# SCH_MCP23X17_smaller_chips_2021-12-25.net
KiCad netlist of a schematic drawn in EasyEDA
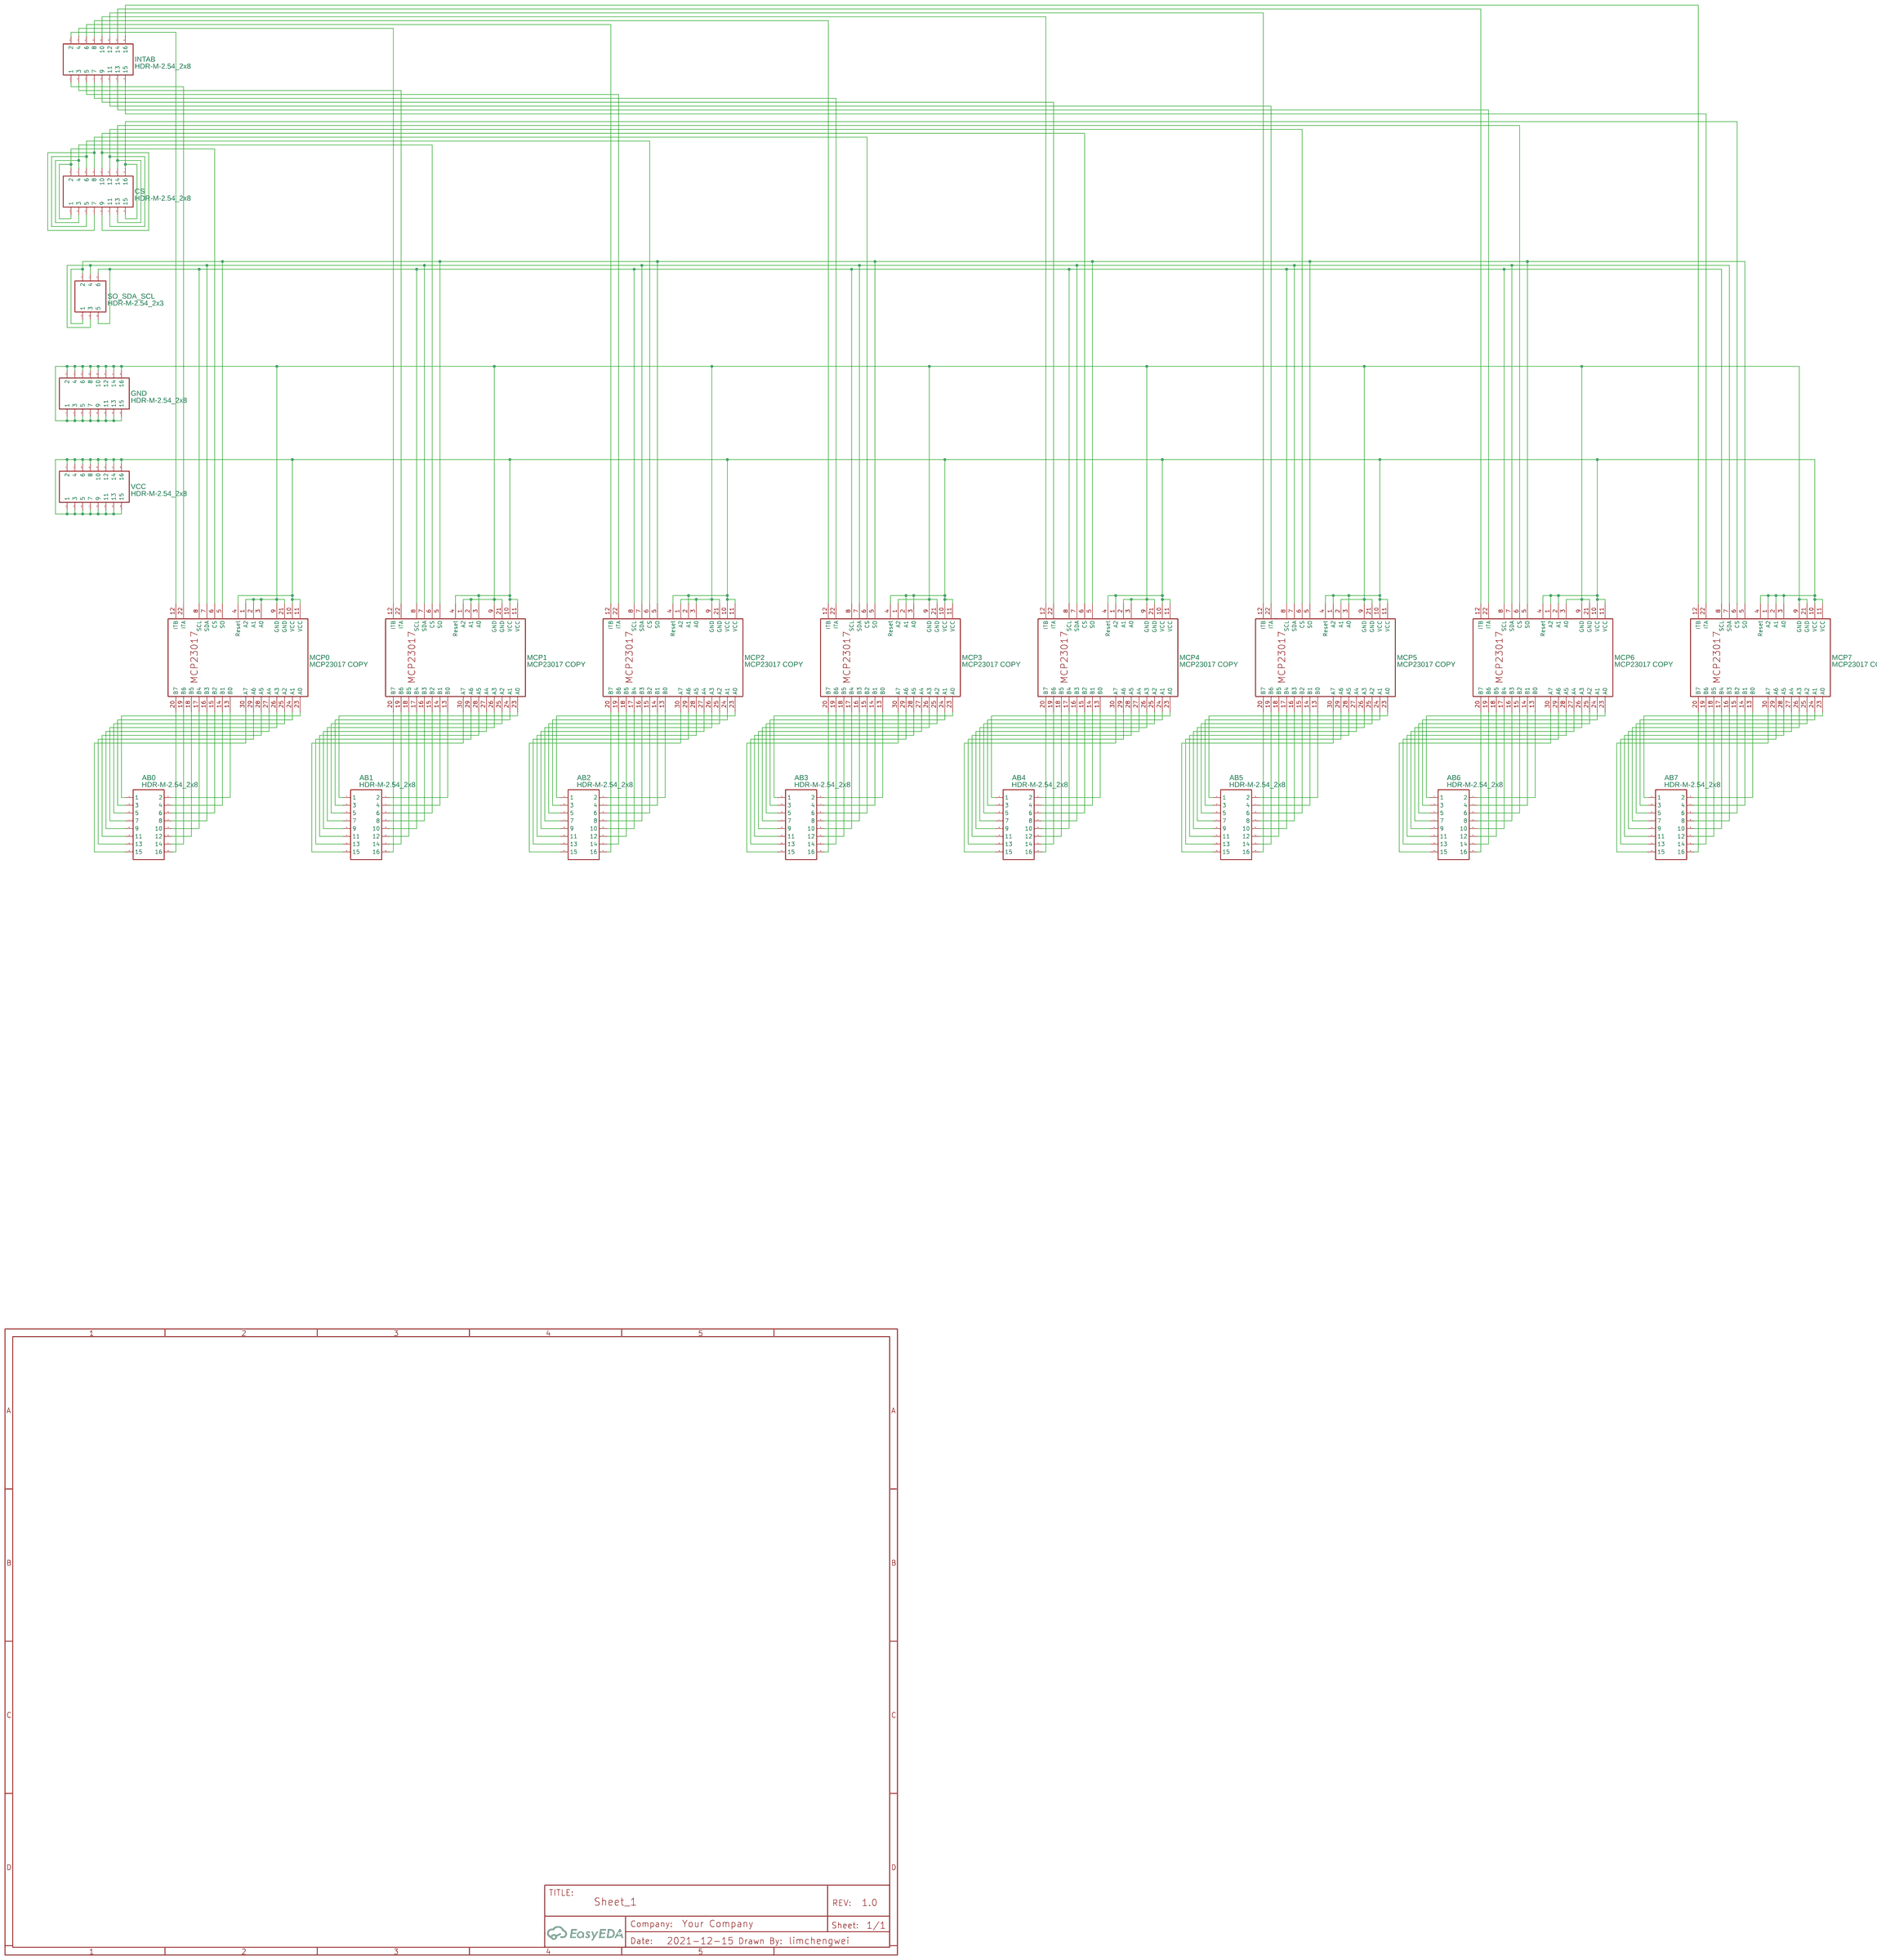
[diagram p0: schematic sheet]

(export (version "E")
  (design (tool "Eeschema 10.0.6"))
  (components
    (comp (ref "AB0")
      (value "HDR-M-2.54_2x8")
      (fields (field (name "BOM_Supplier Part") "C68234"))
      (libsource (lib "") (part "HDR-M-2.54_2x8"))
    )
    (comp (ref "AB1")
      (value "HDR-M-2.54_2x8")
      (fields (field (name "BOM_Supplier Part") "C68234"))
      (libsource (lib "") (part "HDR-M-2.54_2x8"))
    )
    (comp (ref "AB2")
      (value "HDR-M-2.54_2x8")
      (fields (field (name "BOM_Supplier Part") "C68234"))
      (libsource (lib "") (part "HDR-M-2.54_2x8"))
    )
    (comp (ref "AB3")
      (value "HDR-M-2.54_2x8")
      (fields (field (name "BOM_Supplier Part") "C68234"))
      (libsource (lib "") (part "HDR-M-2.54_2x8"))
    )
    (comp (ref "AB4")
      (value "HDR-M-2.54_2x8")
      (fields (field (name "BOM_Supplier Part") "C68234"))
      (libsource (lib "") (part "HDR-M-2.54_2x8"))
    )
    (comp (ref "AB5")
      (value "HDR-M-2.54_2x8")
      (fields (field (name "BOM_Supplier Part") "C68234"))
      (libsource (lib "") (part "HDR-M-2.54_2x8"))
    )
    (comp (ref "AB6")
      (value "HDR-M-2.54_2x8")
      (fields (field (name "BOM_Supplier Part") "C68234"))
      (libsource (lib "") (part "HDR-M-2.54_2x8"))
    )
    (comp (ref "AB7")
      (value "HDR-M-2.54_2x8")
      (fields (field (name "BOM_Supplier Part") "C68234"))
      (libsource (lib "") (part "HDR-M-2.54_2x8"))
    )
    (comp (ref "CS")
      (value "HDR-M-2.54_2x8")
      (fields (field (name "BOM_Supplier Part") "C68234"))
      (libsource (lib "") (part "HDR-M-2.54_2x8_4"))
    )
    (comp (ref "GND")
      (value "HDR-M-2.54_2x8")
      (fields (field (name "BOM_Supplier Part") "C68234"))
      (libsource (lib "") (part "HDR-M-2.54_2x8_3"))
    )
    (comp (ref "INTAB")
      (value "HDR-M-2.54_2x8")
      (fields (field (name "BOM_Supplier Part") "C68234"))
      (libsource (lib "") (part "HDR-M-2.54_2x8_1"))
    )
    (comp (ref "MCP0")
      (value "MCP23017 COPY")
      (fields (field (name "BOM_Manufacturer Part") "MCP23017"))
      (libsource (lib "") (part "MCP23017 COPY"))
    )
    (comp (ref "MCP1")
      (value "MCP23017 COPY")
      (fields (field (name "BOM_Manufacturer Part") "MCP23017"))
      (libsource (lib "") (part "MCP23017 COPY"))
    )
    (comp (ref "MCP2")
      (value "MCP23017 COPY")
      (fields (field (name "BOM_Manufacturer Part") "MCP23017"))
      (libsource (lib "") (part "MCP23017 COPY"))
    )
    (comp (ref "MCP3")
      (value "MCP23017 COPY")
      (fields (field (name "BOM_Manufacturer Part") "MCP23017"))
      (libsource (lib "") (part "MCP23017 COPY"))
    )
    (comp (ref "MCP4")
      (value "MCP23017 COPY")
      (fields (field (name "BOM_Manufacturer Part") "MCP23017"))
      (libsource (lib "") (part "MCP23017 COPY"))
    )
    (comp (ref "MCP5")
      (value "MCP23017 COPY")
      (fields (field (name "BOM_Manufacturer Part") "MCP23017"))
      (libsource (lib "") (part "MCP23017 COPY"))
    )
    (comp (ref "MCP6")
      (value "MCP23017 COPY")
      (fields (field (name "BOM_Manufacturer Part") "MCP23017"))
      (libsource (lib "") (part "MCP23017 COPY"))
    )
    (comp (ref "MCP7")
      (value "MCP23017 COPY")
      (fields (field (name "BOM_Manufacturer Part") "MCP23017"))
      (libsource (lib "") (part "MCP23017 COPY"))
    )
    (comp (ref "SO_SDA_SCL")
      (value "HDR-M-2.54_2x3")
      (fields (field (name "BOM_Supplier Part") "C65114"))
      (libsource (lib "") (part "HDR-M-2.54_2x3"))
    )
    (comp (ref "VCC")
      (value "HDR-M-2.54_2x8")
      (fields (field (name "BOM_Supplier Part") "C68234"))
      (libsource (lib "") (part "HDR-M-2.54_2x8_2"))
    )
  )
  (nets
    (net (code "1") (name "Net-(AB0-Pad1)") (class "Default")
      (node (ref "AB0") (pin "1") (pinfunction "1_1") (pintype "input"))
      (node (ref "MCP0") (pin "23") (pinfunction "A0_23") (pintype "unspecified"))
    )
    (net (code "2") (name "Net-(AB0-Pad3)") (class "Default")
      (node (ref "AB0") (pin "3") (pinfunction "3_3") (pintype "input"))
      (node (ref "MCP0") (pin "24") (pinfunction "A1_24") (pintype "unspecified"))
    )
    (net (code "3") (name "Net-(AB0-Pad5)") (class "Default")
      (node (ref "AB0") (pin "5") (pinfunction "5_5") (pintype "input"))
      (node (ref "MCP0") (pin "25") (pinfunction "A2_25") (pintype "unspecified"))
    )
    (net (code "4") (name "Net-(AB1-Pad1)") (class "Default")
      (node (ref "AB1") (pin "1") (pinfunction "1_1") (pintype "input"))
      (node (ref "MCP1") (pin "23") (pinfunction "A0_23") (pintype "unspecified"))
    )
    (net (code "5") (name "Net-(AB1-Pad3)") (class "Default")
      (node (ref "AB1") (pin "3") (pinfunction "3_3") (pintype "input"))
      (node (ref "MCP1") (pin "24") (pinfunction "A1_24") (pintype "unspecified"))
    )
    (net (code "6") (name "Net-(AB1-Pad5)") (class "Default")
      (node (ref "AB1") (pin "5") (pinfunction "5_5") (pintype "input"))
      (node (ref "MCP1") (pin "25") (pinfunction "A2_25") (pintype "unspecified"))
    )
    (net (code "7") (name "Net-(AB2-Pad1)") (class "Default")
      (node (ref "AB2") (pin "1") (pinfunction "1_1") (pintype "input"))
      (node (ref "MCP2") (pin "23") (pinfunction "A0_23") (pintype "unspecified"))
    )
    (net (code "8") (name "Net-(AB2-Pad3)") (class "Default")
      (node (ref "AB2") (pin "3") (pinfunction "3_3") (pintype "input"))
      (node (ref "MCP2") (pin "24") (pinfunction "A1_24") (pintype "unspecified"))
    )
    (net (code "9") (name "Net-(AB2-Pad5)") (class "Default")
      (node (ref "AB2") (pin "5") (pinfunction "5_5") (pintype "input"))
      (node (ref "MCP2") (pin "25") (pinfunction "A2_25") (pintype "unspecified"))
    )
    (net (code "10") (name "Net-(AB3-Pad1)") (class "Default")
      (node (ref "AB3") (pin "1") (pinfunction "1_1") (pintype "input"))
      (node (ref "MCP3") (pin "23") (pinfunction "A0_23") (pintype "unspecified"))
    )
    (net (code "11") (name "Net-(AB3-Pad3)") (class "Default")
      (node (ref "AB3") (pin "3") (pinfunction "3_3") (pintype "input"))
      (node (ref "MCP3") (pin "24") (pinfunction "A1_24") (pintype "unspecified"))
    )
    (net (code "12") (name "Net-(AB3-Pad5)") (class "Default")
      (node (ref "AB3") (pin "5") (pinfunction "5_5") (pintype "input"))
      (node (ref "MCP3") (pin "25") (pinfunction "A2_25") (pintype "unspecified"))
    )
    (net (code "13") (name "Net-(AB4-Pad1)") (class "Default")
      (node (ref "AB4") (pin "1") (pinfunction "1_1") (pintype "input"))
      (node (ref "MCP4") (pin "23") (pinfunction "A0_23") (pintype "unspecified"))
    )
    (net (code "14") (name "Net-(AB4-Pad3)") (class "Default")
      (node (ref "AB4") (pin "3") (pinfunction "3_3") (pintype "input"))
      (node (ref "MCP4") (pin "24") (pinfunction "A1_24") (pintype "unspecified"))
    )
    (net (code "15") (name "Net-(AB4-Pad5)") (class "Default")
      (node (ref "AB4") (pin "5") (pinfunction "5_5") (pintype "input"))
      (node (ref "MCP4") (pin "25") (pinfunction "A2_25") (pintype "unspecified"))
    )
    (net (code "16") (name "Net-(AB5-Pad1)") (class "Default")
      (node (ref "AB5") (pin "1") (pinfunction "1_1") (pintype "input"))
      (node (ref "MCP5") (pin "23") (pinfunction "A0_23") (pintype "unspecified"))
    )
    (net (code "17") (name "Net-(AB5-Pad3)") (class "Default")
      (node (ref "AB5") (pin "3") (pinfunction "3_3") (pintype "input"))
      (node (ref "MCP5") (pin "24") (pinfunction "A1_24") (pintype "unspecified"))
    )
    (net (code "18") (name "Net-(AB5-Pad5)") (class "Default")
      (node (ref "AB5") (pin "5") (pinfunction "5_5") (pintype "input"))
      (node (ref "MCP5") (pin "25") (pinfunction "A2_25") (pintype "unspecified"))
    )
    (net (code "19") (name "Net-(AB6-Pad1)") (class "Default")
      (node (ref "AB6") (pin "1") (pinfunction "1_1") (pintype "input"))
      (node (ref "MCP6") (pin "23") (pinfunction "A0_23") (pintype "unspecified"))
    )
    (net (code "20") (name "Net-(AB6-Pad3)") (class "Default")
      (node (ref "AB6") (pin "3") (pinfunction "3_3") (pintype "input"))
      (node (ref "MCP6") (pin "24") (pinfunction "A1_24") (pintype "unspecified"))
    )
    (net (code "21") (name "Net-(AB6-Pad5)") (class "Default")
      (node (ref "AB6") (pin "5") (pinfunction "5_5") (pintype "input"))
      (node (ref "MCP6") (pin "25") (pinfunction "A2_25") (pintype "unspecified"))
    )
    (net (code "22") (name "Net-(AB7-Pad1)") (class "Default")
      (node (ref "AB7") (pin "1") (pinfunction "1_1") (pintype "input"))
      (node (ref "MCP7") (pin "23") (pinfunction "A0_23") (pintype "unspecified"))
    )
    (net (code "23") (name "Net-(AB7-Pad3)") (class "Default")
      (node (ref "AB7") (pin "3") (pinfunction "3_3") (pintype "input"))
      (node (ref "MCP7") (pin "24") (pinfunction "A1_24") (pintype "unspecified"))
    )
    (net (code "24") (name "Net-(AB7-Pad5)") (class "Default")
      (node (ref "AB7") (pin "5") (pinfunction "5_5") (pintype "input"))
      (node (ref "MCP7") (pin "25") (pinfunction "A2_25") (pintype "unspecified"))
    )
    (net (code "25") (name "Net-(GND-Pad1)") (class "Default")
      (node (ref "GND") (pin "1") (pinfunction "1_1") (pintype "input"))
      (node (ref "GND") (pin "10") (pinfunction "10_10") (pintype "input"))
      (node (ref "GND") (pin "11") (pinfunction "11_11") (pintype "input"))
      (node (ref "GND") (pin "12") (pinfunction "12_12") (pintype "input"))
      (node (ref "GND") (pin "13") (pinfunction "13_13") (pintype "input"))
      (node (ref "GND") (pin "14") (pinfunction "14_14") (pintype "input"))
      (node (ref "GND") (pin "15") (pinfunction "15_15") (pintype "input"))
      (node (ref "GND") (pin "16") (pinfunction "16_16") (pintype "input"))
      (node (ref "GND") (pin "2") (pinfunction "2_2") (pintype "input"))
      (node (ref "GND") (pin "3") (pinfunction "3_3") (pintype "input"))
      (node (ref "GND") (pin "4") (pinfunction "4_4") (pintype "input"))
      (node (ref "GND") (pin "5") (pinfunction "5_5") (pintype "input"))
      (node (ref "GND") (pin "6") (pinfunction "6_6") (pintype "input"))
      (node (ref "GND") (pin "7") (pinfunction "7_7") (pintype "input"))
      (node (ref "GND") (pin "8") (pinfunction "8_8") (pintype "input"))
      (node (ref "GND") (pin "9") (pinfunction "9_9") (pintype "input"))
      (node (ref "MCP0") (pin "1") (pinfunction "A2_1") (pintype "unspecified"))
      (node (ref "MCP0") (pin "2") (pinfunction "A1_2") (pintype "unspecified"))
      (node (ref "MCP0") (pin "21") (pinfunction "GND_21") (pintype "unspecified"))
      (node (ref "MCP0") (pin "3") (pinfunction "A0_3") (pintype "unspecified"))
      (node (ref "MCP0") (pin "9") (pinfunction "GND_9") (pintype "unspecified"))
      (node (ref "MCP1") (pin "1") (pinfunction "A2_1") (pintype "unspecified"))
      (node (ref "MCP1") (pin "2") (pinfunction "A1_2") (pintype "unspecified"))
      (node (ref "MCP1") (pin "21") (pinfunction "GND_21") (pintype "unspecified"))
      (node (ref "MCP1") (pin "9") (pinfunction "GND_9") (pintype "unspecified"))
      (node (ref "MCP2") (pin "1") (pinfunction "A2_1") (pintype "unspecified"))
      (node (ref "MCP2") (pin "21") (pinfunction "GND_21") (pintype "unspecified"))
      (node (ref "MCP2") (pin "3") (pinfunction "A0_3") (pintype "unspecified"))
      (node (ref "MCP2") (pin "9") (pinfunction "GND_9") (pintype "unspecified"))
      (node (ref "MCP3") (pin "1") (pinfunction "A2_1") (pintype "unspecified"))
      (node (ref "MCP3") (pin "21") (pinfunction "GND_21") (pintype "unspecified"))
      (node (ref "MCP3") (pin "9") (pinfunction "GND_9") (pintype "unspecified"))
      (node (ref "MCP4") (pin "2") (pinfunction "A1_2") (pintype "unspecified"))
      (node (ref "MCP4") (pin "21") (pinfunction "GND_21") (pintype "unspecified"))
      (node (ref "MCP4") (pin "3") (pinfunction "A0_3") (pintype "unspecified"))
      (node (ref "MCP4") (pin "9") (pinfunction "GND_9") (pintype "unspecified"))
      (node (ref "MCP5") (pin "2") (pinfunction "A1_2") (pintype "unspecified"))
      (node (ref "MCP5") (pin "21") (pinfunction "GND_21") (pintype "unspecified"))
      (node (ref "MCP5") (pin "9") (pinfunction "GND_9") (pintype "unspecified"))
      (node (ref "MCP6") (pin "21") (pinfunction "GND_21") (pintype "unspecified"))
      (node (ref "MCP6") (pin "3") (pinfunction "A0_3") (pintype "unspecified"))
      (node (ref "MCP6") (pin "9") (pinfunction "GND_9") (pintype "unspecified"))
      (node (ref "MCP7") (pin "21") (pinfunction "GND_21") (pintype "unspecified"))
      (node (ref "MCP7") (pin "9") (pinfunction "GND_9") (pintype "unspecified"))
    )
    (net (code "26") (name "Net-(MCP0-A3)") (class "Default")
      (node (ref "AB0") (pin "7") (pinfunction "7_7") (pintype "input"))
      (node (ref "MCP0") (pin "26") (pinfunction "A3_26") (pintype "unspecified"))
    )
    (net (code "27") (name "Net-(MCP0-A4)") (class "Default")
      (node (ref "AB0") (pin "9") (pinfunction "9_9") (pintype "input"))
      (node (ref "MCP0") (pin "27") (pinfunction "A4_27") (pintype "unspecified"))
    )
    (net (code "28") (name "Net-(MCP0-A5)") (class "Default")
      (node (ref "AB0") (pin "11") (pinfunction "11_11") (pintype "input"))
      (node (ref "MCP0") (pin "28") (pinfunction "A5_28") (pintype "unspecified"))
    )
    (net (code "29") (name "Net-(MCP0-A6)") (class "Default")
      (node (ref "AB0") (pin "13") (pinfunction "13_13") (pintype "input"))
      (node (ref "MCP0") (pin "29") (pinfunction "A6_29") (pintype "unspecified"))
    )
    (net (code "30") (name "Net-(MCP0-A7)") (class "Default")
      (node (ref "AB0") (pin "15") (pinfunction "15_15") (pintype "input"))
      (node (ref "MCP0") (pin "30") (pinfunction "A7_30") (pintype "unspecified"))
    )
    (net (code "31") (name "Net-(MCP0-B0)") (class "Default")
      (node (ref "AB0") (pin "2") (pinfunction "2_2") (pintype "input"))
      (node (ref "MCP0") (pin "13") (pinfunction "B0_13") (pintype "unspecified"))
    )
    (net (code "32") (name "Net-(MCP0-B1)") (class "Default")
      (node (ref "AB0") (pin "4") (pinfunction "4_4") (pintype "input"))
      (node (ref "MCP0") (pin "14") (pinfunction "B1_14") (pintype "unspecified"))
    )
    (net (code "33") (name "Net-(MCP0-B2)") (class "Default")
      (node (ref "AB0") (pin "6") (pinfunction "6_6") (pintype "input"))
      (node (ref "MCP0") (pin "15") (pinfunction "B2_15") (pintype "unspecified"))
    )
    (net (code "34") (name "Net-(MCP0-B3)") (class "Default")
      (node (ref "AB0") (pin "8") (pinfunction "8_8") (pintype "input"))
      (node (ref "MCP0") (pin "16") (pinfunction "B3_16") (pintype "unspecified"))
    )
    (net (code "35") (name "Net-(MCP0-B4)") (class "Default")
      (node (ref "AB0") (pin "10") (pinfunction "10_10") (pintype "input"))
      (node (ref "MCP0") (pin "17") (pinfunction "B4_17") (pintype "unspecified"))
    )
    (net (code "36") (name "Net-(MCP0-B5)") (class "Default")
      (node (ref "AB0") (pin "12") (pinfunction "12_12") (pintype "input"))
      (node (ref "MCP0") (pin "18") (pinfunction "B5_18") (pintype "unspecified"))
    )
    (net (code "37") (name "Net-(MCP0-B6)") (class "Default")
      (node (ref "AB0") (pin "14") (pinfunction "14_14") (pintype "input"))
      (node (ref "MCP0") (pin "19") (pinfunction "B6_19") (pintype "unspecified"))
    )
    (net (code "38") (name "Net-(MCP0-B7)") (class "Default")
      (node (ref "AB0") (pin "16") (pinfunction "16_16") (pintype "input"))
      (node (ref "MCP0") (pin "20") (pinfunction "B7_20") (pintype "unspecified"))
    )
    (net (code "39") (name "Net-(MCP0-CS)") (class "Default")
      (node (ref "CS") (pin "1") (pinfunction "1_1") (pintype "input"))
      (node (ref "CS") (pin "2") (pinfunction "2_2") (pintype "input"))
      (node (ref "MCP0") (pin "6") (pinfunction "CS_6") (pintype "unspecified"))
    )
    (net (code "40") (name "Net-(MCP0-ITA)") (class "Default")
      (node (ref "INTAB") (pin "1") (pinfunction "1_1") (pintype "input"))
      (node (ref "MCP0") (pin "22") (pinfunction "ITA_22") (pintype "unspecified"))
    )
    (net (code "41") (name "Net-(MCP0-ITB)") (class "Default")
      (node (ref "INTAB") (pin "2") (pinfunction "2_2") (pintype "input"))
      (node (ref "MCP0") (pin "12") (pinfunction "ITB_12") (pintype "unspecified"))
    )
    (net (code "42") (name "Net-(MCP0-Reset)") (class "Default")
      (node (ref "MCP0") (pin "10") (pinfunction "VCC_10") (pintype "unspecified"))
      (node (ref "MCP0") (pin "11") (pinfunction "VCC_11") (pintype "unspecified"))
      (node (ref "MCP0") (pin "4") (pinfunction "Reset_4") (pintype "unspecified"))
      (node (ref "MCP1") (pin "10") (pinfunction "VCC_10") (pintype "unspecified"))
      (node (ref "MCP1") (pin "11") (pinfunction "VCC_11") (pintype "unspecified"))
      (node (ref "MCP1") (pin "3") (pinfunction "A0_3") (pintype "unspecified"))
      (node (ref "MCP1") (pin "4") (pinfunction "Reset_4") (pintype "unspecified"))
      (node (ref "MCP2") (pin "10") (pinfunction "VCC_10") (pintype "unspecified"))
      (node (ref "MCP2") (pin "11") (pinfunction "VCC_11") (pintype "unspecified"))
      (node (ref "MCP2") (pin "2") (pinfunction "A1_2") (pintype "unspecified"))
      (node (ref "MCP2") (pin "4") (pinfunction "Reset_4") (pintype "unspecified"))
      (node (ref "MCP3") (pin "10") (pinfunction "VCC_10") (pintype "unspecified"))
      (node (ref "MCP3") (pin "11") (pinfunction "VCC_11") (pintype "unspecified"))
      (node (ref "MCP3") (pin "2") (pinfunction "A1_2") (pintype "unspecified"))
      (node (ref "MCP3") (pin "3") (pinfunction "A0_3") (pintype "unspecified"))
      (node (ref "MCP3") (pin "4") (pinfunction "Reset_4") (pintype "unspecified"))
      (node (ref "MCP4") (pin "1") (pinfunction "A2_1") (pintype "unspecified"))
      (node (ref "MCP4") (pin "10") (pinfunction "VCC_10") (pintype "unspecified"))
      (node (ref "MCP4") (pin "11") (pinfunction "VCC_11") (pintype "unspecified"))
      (node (ref "MCP4") (pin "4") (pinfunction "Reset_4") (pintype "unspecified"))
      (node (ref "MCP5") (pin "1") (pinfunction "A2_1") (pintype "unspecified"))
      (node (ref "MCP5") (pin "10") (pinfunction "VCC_10") (pintype "unspecified"))
      (node (ref "MCP5") (pin "11") (pinfunction "VCC_11") (pintype "unspecified"))
      (node (ref "MCP5") (pin "3") (pinfunction "A0_3") (pintype "unspecified"))
      (node (ref "MCP5") (pin "4") (pinfunction "Reset_4") (pintype "unspecified"))
      (node (ref "MCP6") (pin "1") (pinfunction "A2_1") (pintype "unspecified"))
      (node (ref "MCP6") (pin "10") (pinfunction "VCC_10") (pintype "unspecified"))
      (node (ref "MCP6") (pin "11") (pinfunction "VCC_11") (pintype "unspecified"))
      (node (ref "MCP6") (pin "2") (pinfunction "A1_2") (pintype "unspecified"))
      (node (ref "MCP6") (pin "4") (pinfunction "Reset_4") (pintype "unspecified"))
      (node (ref "MCP7") (pin "1") (pinfunction "A2_1") (pintype "unspecified"))
      (node (ref "MCP7") (pin "10") (pinfunction "VCC_10") (pintype "unspecified"))
      (node (ref "MCP7") (pin "11") (pinfunction "VCC_11") (pintype "unspecified"))
      (node (ref "MCP7") (pin "2") (pinfunction "A1_2") (pintype "unspecified"))
      (node (ref "MCP7") (pin "3") (pinfunction "A0_3") (pintype "unspecified"))
      (node (ref "MCP7") (pin "4") (pinfunction "Reset_4") (pintype "unspecified"))
      (node (ref "VCC") (pin "1") (pinfunction "1_1") (pintype "input"))
      (node (ref "VCC") (pin "10") (pinfunction "10_10") (pintype "input"))
      (node (ref "VCC") (pin "11") (pinfunction "11_11") (pintype "input"))
      (node (ref "VCC") (pin "12") (pinfunction "12_12") (pintype "input"))
      (node (ref "VCC") (pin "13") (pinfunction "13_13") (pintype "input"))
      (node (ref "VCC") (pin "14") (pinfunction "14_14") (pintype "input"))
      (node (ref "VCC") (pin "15") (pinfunction "15_15") (pintype "input"))
      (node (ref "VCC") (pin "16") (pinfunction "16_16") (pintype "input"))
      (node (ref "VCC") (pin "2") (pinfunction "2_2") (pintype "input"))
      (node (ref "VCC") (pin "3") (pinfunction "3_3") (pintype "input"))
      (node (ref "VCC") (pin "4") (pinfunction "4_4") (pintype "input"))
      (node (ref "VCC") (pin "5") (pinfunction "5_5") (pintype "input"))
      (node (ref "VCC") (pin "6") (pinfunction "6_6") (pintype "input"))
      (node (ref "VCC") (pin "7") (pinfunction "7_7") (pintype "input"))
      (node (ref "VCC") (pin "8") (pinfunction "8_8") (pintype "input"))
      (node (ref "VCC") (pin "9") (pinfunction "9_9") (pintype "input"))
    )
    (net (code "43") (name "Net-(MCP0-SCL)") (class "Default")
      (node (ref "MCP0") (pin "8") (pinfunction "SCL_8") (pintype "unspecified"))
      (node (ref "MCP1") (pin "8") (pinfunction "SCL_8") (pintype "unspecified"))
      (node (ref "MCP2") (pin "8") (pinfunction "SCL_8") (pintype "unspecified"))
      (node (ref "MCP3") (pin "8") (pinfunction "SCL_8") (pintype "unspecified"))
      (node (ref "MCP4") (pin "8") (pinfunction "SCL_8") (pintype "unspecified"))
      (node (ref "MCP5") (pin "8") (pinfunction "SCL_8") (pintype "unspecified"))
      (node (ref "MCP6") (pin "8") (pinfunction "SCL_8") (pintype "unspecified"))
      (node (ref "MCP7") (pin "8") (pinfunction "SCL_8") (pintype "unspecified"))
      (node (ref "SO_SDA_SCL") (pin "5") (pinfunction "5_5") (pintype "input"))
      (node (ref "SO_SDA_SCL") (pin "6") (pinfunction "6_6") (pintype "input"))
    )
    (net (code "44") (name "Net-(MCP0-SDA)") (class "Default")
      (node (ref "MCP0") (pin "7") (pinfunction "SDA_7") (pintype "unspecified"))
      (node (ref "MCP1") (pin "7") (pinfunction "SDA_7") (pintype "unspecified"))
      (node (ref "MCP2") (pin "7") (pinfunction "SDA_7") (pintype "unspecified"))
      (node (ref "MCP3") (pin "7") (pinfunction "SDA_7") (pintype "unspecified"))
      (node (ref "MCP4") (pin "7") (pinfunction "SDA_7") (pintype "unspecified"))
      (node (ref "MCP5") (pin "7") (pinfunction "SDA_7") (pintype "unspecified"))
      (node (ref "MCP6") (pin "7") (pinfunction "SDA_7") (pintype "unspecified"))
      (node (ref "MCP7") (pin "7") (pinfunction "SDA_7") (pintype "unspecified"))
      (node (ref "SO_SDA_SCL") (pin "3") (pinfunction "3_3") (pintype "input"))
      (node (ref "SO_SDA_SCL") (pin "4") (pinfunction "4_4") (pintype "input"))
    )
    (net (code "45") (name "Net-(MCP0-SO)") (class "Default")
      (node (ref "MCP0") (pin "5") (pinfunction "SO_5") (pintype "unspecified"))
      (node (ref "MCP1") (pin "5") (pinfunction "SO_5") (pintype "unspecified"))
      (node (ref "MCP2") (pin "5") (pinfunction "SO_5") (pintype "unspecified"))
      (node (ref "MCP3") (pin "5") (pinfunction "SO_5") (pintype "unspecified"))
      (node (ref "MCP4") (pin "5") (pinfunction "SO_5") (pintype "unspecified"))
      (node (ref "MCP5") (pin "5") (pinfunction "SO_5") (pintype "unspecified"))
      (node (ref "MCP6") (pin "5") (pinfunction "SO_5") (pintype "unspecified"))
      (node (ref "MCP7") (pin "5") (pinfunction "SO_5") (pintype "unspecified"))
      (node (ref "SO_SDA_SCL") (pin "1") (pinfunction "1_1") (pintype "input"))
      (node (ref "SO_SDA_SCL") (pin "2") (pinfunction "2_2") (pintype "input"))
    )
    (net (code "46") (name "Net-(MCP1-A3)") (class "Default")
      (node (ref "AB1") (pin "7") (pinfunction "7_7") (pintype "input"))
      (node (ref "MCP1") (pin "26") (pinfunction "A3_26") (pintype "unspecified"))
    )
    (net (code "47") (name "Net-(MCP1-A4)") (class "Default")
      (node (ref "AB1") (pin "9") (pinfunction "9_9") (pintype "input"))
      (node (ref "MCP1") (pin "27") (pinfunction "A4_27") (pintype "unspecified"))
    )
    (net (code "48") (name "Net-(MCP1-A5)") (class "Default")
      (node (ref "AB1") (pin "11") (pinfunction "11_11") (pintype "input"))
      (node (ref "MCP1") (pin "28") (pinfunction "A5_28") (pintype "unspecified"))
    )
    (net (code "49") (name "Net-(MCP1-A6)") (class "Default")
      (node (ref "AB1") (pin "13") (pinfunction "13_13") (pintype "input"))
      (node (ref "MCP1") (pin "29") (pinfunction "A6_29") (pintype "unspecified"))
    )
    (net (code "50") (name "Net-(MCP1-A7)") (class "Default")
      (node (ref "AB1") (pin "15") (pinfunction "15_15") (pintype "input"))
      (node (ref "MCP1") (pin "30") (pinfunction "A7_30") (pintype "unspecified"))
    )
    (net (code "51") (name "Net-(MCP1-B0)") (class "Default")
      (node (ref "AB1") (pin "2") (pinfunction "2_2") (pintype "input"))
      (node (ref "MCP1") (pin "13") (pinfunction "B0_13") (pintype "unspecified"))
    )
    (net (code "52") (name "Net-(MCP1-B1)") (class "Default")
      (node (ref "AB1") (pin "4") (pinfunction "4_4") (pintype "input"))
      (node (ref "MCP1") (pin "14") (pinfunction "B1_14") (pintype "unspecified"))
    )
    (net (code "53") (name "Net-(MCP1-B2)") (class "Default")
      (node (ref "AB1") (pin "6") (pinfunction "6_6") (pintype "input"))
      (node (ref "MCP1") (pin "15") (pinfunction "B2_15") (pintype "unspecified"))
    )
    (net (code "54") (name "Net-(MCP1-B3)") (class "Default")
      (node (ref "AB1") (pin "8") (pinfunction "8_8") (pintype "input"))
      (node (ref "MCP1") (pin "16") (pinfunction "B3_16") (pintype "unspecified"))
    )
    (net (code "55") (name "Net-(MCP1-B4)") (class "Default")
      (node (ref "AB1") (pin "10") (pinfunction "10_10") (pintype "input"))
      (node (ref "MCP1") (pin "17") (pinfunction "B4_17") (pintype "unspecified"))
    )
    (net (code "56") (name "Net-(MCP1-B5)") (class "Default")
      (node (ref "AB1") (pin "12") (pinfunction "12_12") (pintype "input"))
      (node (ref "MCP1") (pin "18") (pinfunction "B5_18") (pintype "unspecified"))
    )
    (net (code "57") (name "Net-(MCP1-B6)") (class "Default")
      (node (ref "AB1") (pin "14") (pinfunction "14_14") (pintype "input"))
      (node (ref "MCP1") (pin "19") (pinfunction "B6_19") (pintype "unspecified"))
    )
    (net (code "58") (name "Net-(MCP1-B7)") (class "Default")
      (node (ref "AB1") (pin "16") (pinfunction "16_16") (pintype "input"))
      (node (ref "MCP1") (pin "20") (pinfunction "B7_20") (pintype "unspecified"))
    )
    (net (code "59") (name "Net-(MCP1-CS)") (class "Default")
      (node (ref "CS") (pin "3") (pinfunction "3_3") (pintype "input"))
      (node (ref "CS") (pin "4") (pinfunction "4_4") (pintype "input"))
      (node (ref "MCP1") (pin "6") (pinfunction "CS_6") (pintype "unspecified"))
    )
    (net (code "60") (name "Net-(MCP1-ITA)") (class "Default")
      (node (ref "INTAB") (pin "3") (pinfunction "3_3") (pintype "input"))
      (node (ref "MCP1") (pin "22") (pinfunction "ITA_22") (pintype "unspecified"))
    )
    (net (code "61") (name "Net-(MCP1-ITB)") (class "Default")
      (node (ref "INTAB") (pin "4") (pinfunction "4_4") (pintype "input"))
      (node (ref "MCP1") (pin "12") (pinfunction "ITB_12") (pintype "unspecified"))
    )
    (net (code "62") (name "Net-(MCP2-A3)") (class "Default")
      (node (ref "AB2") (pin "7") (pinfunction "7_7") (pintype "input"))
      (node (ref "MCP2") (pin "26") (pinfunction "A3_26") (pintype "unspecified"))
    )
    (net (code "63") (name "Net-(MCP2-A4)") (class "Default")
      (node (ref "AB2") (pin "9") (pinfunction "9_9") (pintype "input"))
      (node (ref "MCP2") (pin "27") (pinfunction "A4_27") (pintype "unspecified"))
    )
    (net (code "64") (name "Net-(MCP2-A5)") (class "Default")
      (node (ref "AB2") (pin "11") (pinfunction "11_11") (pintype "input"))
      (node (ref "MCP2") (pin "28") (pinfunction "A5_28") (pintype "unspecified"))
    )
    (net (code "65") (name "Net-(MCP2-A6)") (class "Default")
      (node (ref "AB2") (pin "13") (pinfunction "13_13") (pintype "input"))
      (node (ref "MCP2") (pin "29") (pinfunction "A6_29") (pintype "unspecified"))
    )
    (net (code "66") (name "Net-(MCP2-A7)") (class "Default")
      (node (ref "AB2") (pin "15") (pinfunction "15_15") (pintype "input"))
      (node (ref "MCP2") (pin "30") (pinfunction "A7_30") (pintype "unspecified"))
    )
    (net (code "67") (name "Net-(MCP2-B0)") (class "Default")
      (node (ref "AB2") (pin "2") (pinfunction "2_2") (pintype "input"))
      (node (ref "MCP2") (pin "13") (pinfunction "B0_13") (pintype "unspecified"))
    )
    (net (code "68") (name "Net-(MCP2-B1)") (class "Default")
      (node (ref "AB2") (pin "4") (pinfunction "4_4") (pintype "input"))
      (node (ref "MCP2") (pin "14") (pinfunction "B1_14") (pintype "unspecified"))
    )
    (net (code "69") (name "Net-(MCP2-B2)") (class "Default")
      (node (ref "AB2") (pin "6") (pinfunction "6_6") (pintype "input"))
      (node (ref "MCP2") (pin "15") (pinfunction "B2_15") (pintype "unspecified"))
    )
    (net (code "70") (name "Net-(MCP2-B3)") (class "Default")
      (node (ref "AB2") (pin "8") (pinfunction "8_8") (pintype "input"))
      (node (ref "MCP2") (pin "16") (pinfunction "B3_16") (pintype "unspecified"))
    )
    (net (code "71") (name "Net-(MCP2-B4)") (class "Default")
      (node (ref "AB2") (pin "10") (pinfunction "10_10") (pintype "input"))
      (node (ref "MCP2") (pin "17") (pinfunction "B4_17") (pintype "unspecified"))
    )
    (net (code "72") (name "Net-(MCP2-B5)") (class "Default")
      (node (ref "AB2") (pin "12") (pinfunction "12_12") (pintype "input"))
      (node (ref "MCP2") (pin "18") (pinfunction "B5_18") (pintype "unspecified"))
    )
    (net (code "73") (name "Net-(MCP2-B6)") (class "Default")
      (node (ref "AB2") (pin "14") (pinfunction "14_14") (pintype "input"))
      (node (ref "MCP2") (pin "19") (pinfunction "B6_19") (pintype "unspecified"))
    )
    (net (code "74") (name "Net-(MCP2-B7)") (class "Default")
      (node (ref "AB2") (pin "16") (pinfunction "16_16") (pintype "input"))
      (node (ref "MCP2") (pin "20") (pinfunction "B7_20") (pintype "unspecified"))
    )
    (net (code "75") (name "Net-(MCP2-CS)") (class "Default")
      (node (ref "CS") (pin "5") (pinfunction "5_5") (pintype "input"))
      (node (ref "CS") (pin "6") (pinfunction "6_6") (pintype "input"))
      (node (ref "MCP2") (pin "6") (pinfunction "CS_6") (pintype "unspecified"))
    )
    (net (code "76") (name "Net-(MCP2-ITA)") (class "Default")
      (node (ref "INTAB") (pin "5") (pinfunction "5_5") (pintype "input"))
      (node (ref "MCP2") (pin "22") (pinfunction "ITA_22") (pintype "unspecified"))
    )
    (net (code "77") (name "Net-(MCP2-ITB)") (class "Default")
      (node (ref "INTAB") (pin "6") (pinfunction "6_6") (pintype "input"))
      (node (ref "MCP2") (pin "12") (pinfunction "ITB_12") (pintype "unspecified"))
    )
    (net (code "78") (name "Net-(MCP3-A3)") (class "Default")
      (node (ref "AB3") (pin "7") (pinfunction "7_7") (pintype "input"))
      (node (ref "MCP3") (pin "26") (pinfunction "A3_26") (pintype "unspecified"))
    )
    (net (code "79") (name "Net-(MCP3-A4)") (class "Default")
      (node (ref "AB3") (pin "9") (pinfunction "9_9") (pintype "input"))
      (node (ref "MCP3") (pin "27") (pinfunction "A4_27") (pintype "unspecified"))
    )
    (net (code "80") (name "Net-(MCP3-A5)") (class "Default")
      (node (ref "AB3") (pin "11") (pinfunction "11_11") (pintype "input"))
      (node (ref "MCP3") (pin "28") (pinfunction "A5_28") (pintype "unspecified"))
    )
    (net (code "81") (name "Net-(MCP3-A6)") (class "Default")
      (node (ref "AB3") (pin "13") (pinfunction "13_13") (pintype "input"))
      (node (ref "MCP3") (pin "29") (pinfunction "A6_29") (pintype "unspecified"))
    )
    (net (code "82") (name "Net-(MCP3-A7)") (class "Default")
      (node (ref "AB3") (pin "15") (pinfunction "15_15") (pintype "input"))
      (node (ref "MCP3") (pin "30") (pinfunction "A7_30") (pintype "unspecified"))
    )
    (net (code "83") (name "Net-(MCP3-B0)") (class "Default")
      (node (ref "AB3") (pin "2") (pinfunction "2_2") (pintype "input"))
      (node (ref "MCP3") (pin "13") (pinfunction "B0_13") (pintype "unspecified"))
    )
    (net (code "84") (name "Net-(MCP3-B1)") (class "Default")
      (node (ref "AB3") (pin "4") (pinfunction "4_4") (pintype "input"))
      (node (ref "MCP3") (pin "14") (pinfunction "B1_14") (pintype "unspecified"))
    )
    (net (code "85") (name "Net-(MCP3-B2)") (class "Default")
      (node (ref "AB3") (pin "6") (pinfunction "6_6") (pintype "input"))
      (node (ref "MCP3") (pin "15") (pinfunction "B2_15") (pintype "unspecified"))
    )
    (net (code "86") (name "Net-(MCP3-B3)") (class "Default")
      (node (ref "AB3") (pin "8") (pinfunction "8_8") (pintype "input"))
      (node (ref "MCP3") (pin "16") (pinfunction "B3_16") (pintype "unspecified"))
    )
    (net (code "87") (name "Net-(MCP3-B4)") (class "Default")
      (node (ref "AB3") (pin "10") (pinfunction "10_10") (pintype "input"))
      (node (ref "MCP3") (pin "17") (pinfunction "B4_17") (pintype "unspecified"))
    )
    (net (code "88") (name "Net-(MCP3-B5)") (class "Default")
      (node (ref "AB3") (pin "12") (pinfunction "12_12") (pintype "input"))
      (node (ref "MCP3") (pin "18") (pinfunction "B5_18") (pintype "unspecified"))
    )
    (net (code "89") (name "Net-(MCP3-B6)") (class "Default")
      (node (ref "AB3") (pin "14") (pinfunction "14_14") (pintype "input"))
      (node (ref "MCP3") (pin "19") (pinfunction "B6_19") (pintype "unspecified"))
    )
    (net (code "90") (name "Net-(MCP3-B7)") (class "Default")
      (node (ref "AB3") (pin "16") (pinfunction "16_16") (pintype "input"))
      (node (ref "MCP3") (pin "20") (pinfunction "B7_20") (pintype "unspecified"))
    )
    (net (code "91") (name "Net-(MCP3-CS)") (class "Default")
      (node (ref "CS") (pin "7") (pinfunction "7_7") (pintype "input"))
      (node (ref "CS") (pin "8") (pinfunction "8_8") (pintype "input"))
      (node (ref "MCP3") (pin "6") (pinfunction "CS_6") (pintype "unspecified"))
    )
    (net (code "92") (name "Net-(MCP3-ITA)") (class "Default")
      (node (ref "INTAB") (pin "7") (pinfunction "7_7") (pintype "input"))
      (node (ref "MCP3") (pin "22") (pinfunction "ITA_22") (pintype "unspecified"))
    )
    (net (code "93") (name "Net-(MCP3-ITB)") (class "Default")
      (node (ref "INTAB") (pin "8") (pinfunction "8_8") (pintype "input"))
      (node (ref "MCP3") (pin "12") (pinfunction "ITB_12") (pintype "unspecified"))
    )
    (net (code "94") (name "Net-(MCP4-A3)") (class "Default")
      (node (ref "AB4") (pin "7") (pinfunction "7_7") (pintype "input"))
      (node (ref "MCP4") (pin "26") (pinfunction "A3_26") (pintype "unspecified"))
    )
    (net (code "95") (name "Net-(MCP4-A4)") (class "Default")
      (node (ref "AB4") (pin "9") (pinfunction "9_9") (pintype "input"))
      (node (ref "MCP4") (pin "27") (pinfunction "A4_27") (pintype "unspecified"))
    )
    (net (code "96") (name "Net-(MCP4-A5)") (class "Default")
      (node (ref "AB4") (pin "11") (pinfunction "11_11") (pintype "input"))
      (node (ref "MCP4") (pin "28") (pinfunction "A5_28") (pintype "unspecified"))
    )
    (net (code "97") (name "Net-(MCP4-A6)") (class "Default")
      (node (ref "AB4") (pin "13") (pinfunction "13_13") (pintype "input"))
      (node (ref "MCP4") (pin "29") (pinfunction "A6_29") (pintype "unspecified"))
    )
    (net (code "98") (name "Net-(MCP4-A7)") (class "Default")
      (node (ref "AB4") (pin "15") (pinfunction "15_15") (pintype "input"))
      (node (ref "MCP4") (pin "30") (pinfunction "A7_30") (pintype "unspecified"))
    )
    (net (code "99") (name "Net-(MCP4-B0)") (class "Default")
      (node (ref "AB4") (pin "2") (pinfunction "2_2") (pintype "input"))
      (node (ref "MCP4") (pin "13") (pinfunction "B0_13") (pintype "unspecified"))
    )
    (net (code "100") (name "Net-(MCP4-B1)") (class "Default")
      (node (ref "AB4") (pin "4") (pinfunction "4_4") (pintype "input"))
      (node (ref "MCP4") (pin "14") (pinfunction "B1_14") (pintype "unspecified"))
    )
    (net (code "101") (name "Net-(MCP4-B2)") (class "Default")
      (node (ref "AB4") (pin "6") (pinfunction "6_6") (pintype "input"))
      (node (ref "MCP4") (pin "15") (pinfunction "B2_15") (pintype "unspecified"))
    )
    (net (code "102") (name "Net-(MCP4-B3)") (class "Default")
      (node (ref "AB4") (pin "8") (pinfunction "8_8") (pintype "input"))
      (node (ref "MCP4") (pin "16") (pinfunction "B3_16") (pintype "unspecified"))
    )
    (net (code "103") (name "Net-(MCP4-B4)") (class "Default")
      (node (ref "AB4") (pin "10") (pinfunction "10_10") (pintype "input"))
      (node (ref "MCP4") (pin "17") (pinfunction "B4_17") (pintype "unspecified"))
    )
    (net (code "104") (name "Net-(MCP4-B5)") (class "Default")
      (node (ref "AB4") (pin "12") (pinfunction "12_12") (pintype "input"))
      (node (ref "MCP4") (pin "18") (pinfunction "B5_18") (pintype "unspecified"))
    )
    (net (code "105") (name "Net-(MCP4-B6)") (class "Default")
      (node (ref "AB4") (pin "14") (pinfunction "14_14") (pintype "input"))
      (node (ref "MCP4") (pin "19") (pinfunction "B6_19") (pintype "unspecified"))
    )
    (net (code "106") (name "Net-(MCP4-B7)") (class "Default")
      (node (ref "AB4") (pin "16") (pinfunction "16_16") (pintype "input"))
      (node (ref "MCP4") (pin "20") (pinfunction "B7_20") (pintype "unspecified"))
    )
    (net (code "107") (name "Net-(MCP4-CS)") (class "Default")
      (node (ref "CS") (pin "10") (pinfunction "10_10") (pintype "input"))
      (node (ref "CS") (pin "9") (pinfunction "9_9") (pintype "input"))
      (node (ref "MCP4") (pin "6") (pinfunction "CS_6") (pintype "unspecified"))
    )
    (net (code "108") (name "Net-(MCP4-ITA)") (class "Default")
      (node (ref "INTAB") (pin "9") (pinfunction "9_9") (pintype "input"))
      (node (ref "MCP4") (pin "22") (pinfunction "ITA_22") (pintype "unspecified"))
    )
    (net (code "109") (name "Net-(MCP4-ITB)") (class "Default")
      (node (ref "INTAB") (pin "10") (pinfunction "10_10") (pintype "input"))
      (node (ref "MCP4") (pin "12") (pinfunction "ITB_12") (pintype "unspecified"))
    )
    (net (code "110") (name "Net-(MCP5-A3)") (class "Default")
      (node (ref "AB5") (pin "7") (pinfunction "7_7") (pintype "input"))
      (node (ref "MCP5") (pin "26") (pinfunction "A3_26") (pintype "unspecified"))
    )
    (net (code "111") (name "Net-(MCP5-A4)") (class "Default")
      (node (ref "AB5") (pin "9") (pinfunction "9_9") (pintype "input"))
      (node (ref "MCP5") (pin "27") (pinfunction "A4_27") (pintype "unspecified"))
    )
    (net (code "112") (name "Net-(MCP5-A5)") (class "Default")
      (node (ref "AB5") (pin "11") (pinfunction "11_11") (pintype "input"))
      (node (ref "MCP5") (pin "28") (pinfunction "A5_28") (pintype "unspecified"))
    )
    (net (code "113") (name "Net-(MCP5-A6)") (class "Default")
      (node (ref "AB5") (pin "13") (pinfunction "13_13") (pintype "input"))
      (node (ref "MCP5") (pin "29") (pinfunction "A6_29") (pintype "unspecified"))
    )
    (net (code "114") (name "Net-(MCP5-A7)") (class "Default")
      (node (ref "AB5") (pin "15") (pinfunction "15_15") (pintype "input"))
      (node (ref "MCP5") (pin "30") (pinfunction "A7_30") (pintype "unspecified"))
    )
    (net (code "115") (name "Net-(MCP5-B0)") (class "Default")
      (node (ref "AB5") (pin "2") (pinfunction "2_2") (pintype "input"))
      (node (ref "MCP5") (pin "13") (pinfunction "B0_13") (pintype "unspecified"))
    )
    (net (code "116") (name "Net-(MCP5-B1)") (class "Default")
      (node (ref "AB5") (pin "4") (pinfunction "4_4") (pintype "input"))
      (node (ref "MCP5") (pin "14") (pinfunction "B1_14") (pintype "unspecified"))
    )
    (net (code "117") (name "Net-(MCP5-B2)") (class "Default")
      (node (ref "AB5") (pin "6") (pinfunction "6_6") (pintype "input"))
      (node (ref "MCP5") (pin "15") (pinfunction "B2_15") (pintype "unspecified"))
    )
    (net (code "118") (name "Net-(MCP5-B3)") (class "Default")
      (node (ref "AB5") (pin "8") (pinfunction "8_8") (pintype "input"))
      (node (ref "MCP5") (pin "16") (pinfunction "B3_16") (pintype "unspecified"))
    )
    (net (code "119") (name "Net-(MCP5-B4)") (class "Default")
      (node (ref "AB5") (pin "10") (pinfunction "10_10") (pintype "input"))
      (node (ref "MCP5") (pin "17") (pinfunction "B4_17") (pintype "unspecified"))
    )
    (net (code "120") (name "Net-(MCP5-B5)") (class "Default")
      (node (ref "AB5") (pin "12") (pinfunction "12_12") (pintype "input"))
      (node (ref "MCP5") (pin "18") (pinfunction "B5_18") (pintype "unspecified"))
    )
    (net (code "121") (name "Net-(MCP5-B6)") (class "Default")
      (node (ref "AB5") (pin "14") (pinfunction "14_14") (pintype "input"))
      (node (ref "MCP5") (pin "19") (pinfunction "B6_19") (pintype "unspecified"))
    )
    (net (code "122") (name "Net-(MCP5-B7)") (class "Default")
      (node (ref "AB5") (pin "16") (pinfunction "16_16") (pintype "input"))
      (node (ref "MCP5") (pin "20") (pinfunction "B7_20") (pintype "unspecified"))
    )
    (net (code "123") (name "Net-(MCP5-CS)") (class "Default")
      (node (ref "CS") (pin "11") (pinfunction "11_11") (pintype "input"))
      (node (ref "CS") (pin "12") (pinfunction "12_12") (pintype "input"))
      (node (ref "MCP5") (pin "6") (pinfunction "CS_6") (pintype "unspecified"))
    )
    (net (code "124") (name "Net-(MCP5-ITA)") (class "Default")
      (node (ref "INTAB") (pin "11") (pinfunction "11_11") (pintype "input"))
      (node (ref "MCP5") (pin "22") (pinfunction "ITA_22") (pintype "unspecified"))
    )
    (net (code "125") (name "Net-(MCP5-ITB)") (class "Default")
      (node (ref "INTAB") (pin "12") (pinfunction "12_12") (pintype "input"))
      (node (ref "MCP5") (pin "12") (pinfunction "ITB_12") (pintype "unspecified"))
    )
    (net (code "126") (name "Net-(MCP6-A3)") (class "Default")
      (node (ref "AB6") (pin "7") (pinfunction "7_7") (pintype "input"))
      (node (ref "MCP6") (pin "26") (pinfunction "A3_26") (pintype "unspecified"))
    )
    (net (code "127") (name "Net-(MCP6-A4)") (class "Default")
      (node (ref "AB6") (pin "9") (pinfunction "9_9") (pintype "input"))
      (node (ref "MCP6") (pin "27") (pinfunction "A4_27") (pintype "unspecified"))
    )
    (net (code "128") (name "Net-(MCP6-A5)") (class "Default")
      (node (ref "AB6") (pin "11") (pinfunction "11_11") (pintype "input"))
      (node (ref "MCP6") (pin "28") (pinfunction "A5_28") (pintype "unspecified"))
    )
    (net (code "129") (name "Net-(MCP6-A6)") (class "Default")
      (node (ref "AB6") (pin "13") (pinfunction "13_13") (pintype "input"))
      (node (ref "MCP6") (pin "29") (pinfunction "A6_29") (pintype "unspecified"))
    )
    (net (code "130") (name "Net-(MCP6-A7)") (class "Default")
      (node (ref "AB6") (pin "15") (pinfunction "15_15") (pintype "input"))
      (node (ref "MCP6") (pin "30") (pinfunction "A7_30") (pintype "unspecified"))
    )
    (net (code "131") (name "Net-(MCP6-B0)") (class "Default")
      (node (ref "AB6") (pin "2") (pinfunction "2_2") (pintype "input"))
      (node (ref "MCP6") (pin "13") (pinfunction "B0_13") (pintype "unspecified"))
    )
    (net (code "132") (name "Net-(MCP6-B1)") (class "Default")
      (node (ref "AB6") (pin "4") (pinfunction "4_4") (pintype "input"))
      (node (ref "MCP6") (pin "14") (pinfunction "B1_14") (pintype "unspecified"))
    )
    (net (code "133") (name "Net-(MCP6-B2)") (class "Default")
      (node (ref "AB6") (pin "6") (pinfunction "6_6") (pintype "input"))
      (node (ref "MCP6") (pin "15") (pinfunction "B2_15") (pintype "unspecified"))
    )
    (net (code "134") (name "Net-(MCP6-B3)") (class "Default")
      (node (ref "AB6") (pin "8") (pinfunction "8_8") (pintype "input"))
      (node (ref "MCP6") (pin "16") (pinfunction "B3_16") (pintype "unspecified"))
    )
    (net (code "135") (name "Net-(MCP6-B4)") (class "Default")
      (node (ref "AB6") (pin "10") (pinfunction "10_10") (pintype "input"))
      (node (ref "MCP6") (pin "17") (pinfunction "B4_17") (pintype "unspecified"))
    )
    (net (code "136") (name "Net-(MCP6-B5)") (class "Default")
      (node (ref "AB6") (pin "12") (pinfunction "12_12") (pintype "input"))
      (node (ref "MCP6") (pin "18") (pinfunction "B5_18") (pintype "unspecified"))
    )
    (net (code "137") (name "Net-(MCP6-B6)") (class "Default")
      (node (ref "AB6") (pin "14") (pinfunction "14_14") (pintype "input"))
      (node (ref "MCP6") (pin "19") (pinfunction "B6_19") (pintype "unspecified"))
    )
    (net (code "138") (name "Net-(MCP6-B7)") (class "Default")
      (node (ref "AB6") (pin "16") (pinfunction "16_16") (pintype "input"))
      (node (ref "MCP6") (pin "20") (pinfunction "B7_20") (pintype "unspecified"))
    )
    (net (code "139") (name "Net-(MCP6-CS)") (class "Default")
      (node (ref "CS") (pin "13") (pinfunction "13_13") (pintype "input"))
      (node (ref "CS") (pin "14") (pinfunction "14_14") (pintype "input"))
      (node (ref "MCP6") (pin "6") (pinfunction "CS_6") (pintype "unspecified"))
    )
    (net (code "140") (name "Net-(MCP6-ITA)") (class "Default")
      (node (ref "INTAB") (pin "13") (pinfunction "13_13") (pintype "input"))
      (node (ref "MCP6") (pin "22") (pinfunction "ITA_22") (pintype "unspecified"))
    )
    (net (code "141") (name "Net-(MCP6-ITB)") (class "Default")
      (node (ref "INTAB") (pin "14") (pinfunction "14_14") (pintype "input"))
      (node (ref "MCP6") (pin "12") (pinfunction "ITB_12") (pintype "unspecified"))
    )
    (net (code "142") (name "Net-(MCP7-A3)") (class "Default")
      (node (ref "AB7") (pin "7") (pinfunction "7_7") (pintype "input"))
      (node (ref "MCP7") (pin "26") (pinfunction "A3_26") (pintype "unspecified"))
    )
    (net (code "143") (name "Net-(MCP7-A4)") (class "Default")
      (node (ref "AB7") (pin "9") (pinfunction "9_9") (pintype "input"))
      (node (ref "MCP7") (pin "27") (pinfunction "A4_27") (pintype "unspecified"))
    )
    (net (code "144") (name "Net-(MCP7-A5)") (class "Default")
      (node (ref "AB7") (pin "11") (pinfunction "11_11") (pintype "input"))
      (node (ref "MCP7") (pin "28") (pinfunction "A5_28") (pintype "unspecified"))
    )
    (net (code "145") (name "Net-(MCP7-A6)") (class "Default")
      (node (ref "AB7") (pin "13") (pinfunction "13_13") (pintype "input"))
      (node (ref "MCP7") (pin "29") (pinfunction "A6_29") (pintype "unspecified"))
    )
    (net (code "146") (name "Net-(MCP7-A7)") (class "Default")
      (node (ref "AB7") (pin "15") (pinfunction "15_15") (pintype "input"))
      (node (ref "MCP7") (pin "30") (pinfunction "A7_30") (pintype "unspecified"))
    )
    (net (code "147") (name "Net-(MCP7-B0)") (class "Default")
      (node (ref "AB7") (pin "2") (pinfunction "2_2") (pintype "input"))
      (node (ref "MCP7") (pin "13") (pinfunction "B0_13") (pintype "unspecified"))
    )
    (net (code "148") (name "Net-(MCP7-B1)") (class "Default")
      (node (ref "AB7") (pin "4") (pinfunction "4_4") (pintype "input"))
      (node (ref "MCP7") (pin "14") (pinfunction "B1_14") (pintype "unspecified"))
    )
    (net (code "149") (name "Net-(MCP7-B2)") (class "Default")
      (node (ref "AB7") (pin "6") (pinfunction "6_6") (pintype "input"))
      (node (ref "MCP7") (pin "15") (pinfunction "B2_15") (pintype "unspecified"))
    )
    (net (code "150") (name "Net-(MCP7-B3)") (class "Default")
      (node (ref "AB7") (pin "8") (pinfunction "8_8") (pintype "input"))
      (node (ref "MCP7") (pin "16") (pinfunction "B3_16") (pintype "unspecified"))
    )
    (net (code "151") (name "Net-(MCP7-B4)") (class "Default")
      (node (ref "AB7") (pin "10") (pinfunction "10_10") (pintype "input"))
      (node (ref "MCP7") (pin "17") (pinfunction "B4_17") (pintype "unspecified"))
    )
    (net (code "152") (name "Net-(MCP7-B5)") (class "Default")
      (node (ref "AB7") (pin "12") (pinfunction "12_12") (pintype "input"))
      (node (ref "MCP7") (pin "18") (pinfunction "B5_18") (pintype "unspecified"))
    )
    (net (code "153") (name "Net-(MCP7-B6)") (class "Default")
      (node (ref "AB7") (pin "14") (pinfunction "14_14") (pintype "input"))
      (node (ref "MCP7") (pin "19") (pinfunction "B6_19") (pintype "unspecified"))
    )
    (net (code "154") (name "Net-(MCP7-B7)") (class "Default")
      (node (ref "AB7") (pin "16") (pinfunction "16_16") (pintype "input"))
      (node (ref "MCP7") (pin "20") (pinfunction "B7_20") (pintype "unspecified"))
    )
    (net (code "155") (name "Net-(MCP7-CS)") (class "Default")
      (node (ref "CS") (pin "15") (pinfunction "15_15") (pintype "input"))
      (node (ref "CS") (pin "16") (pinfunction "16_16") (pintype "input"))
      (node (ref "MCP7") (pin "6") (pinfunction "CS_6") (pintype "unspecified"))
    )
    (net (code "156") (name "Net-(MCP7-ITA)") (class "Default")
      (node (ref "INTAB") (pin "15") (pinfunction "15_15") (pintype "input"))
      (node (ref "MCP7") (pin "22") (pinfunction "ITA_22") (pintype "unspecified"))
    )
    (net (code "157") (name "Net-(MCP7-ITB)") (class "Default")
      (node (ref "INTAB") (pin "16") (pinfunction "16_16") (pintype "input"))
      (node (ref "MCP7") (pin "12") (pinfunction "ITB_12") (pintype "unspecified"))
    )
  )
)
